# buses.net
KiCad netlist of a schematic drawn in EAGLE
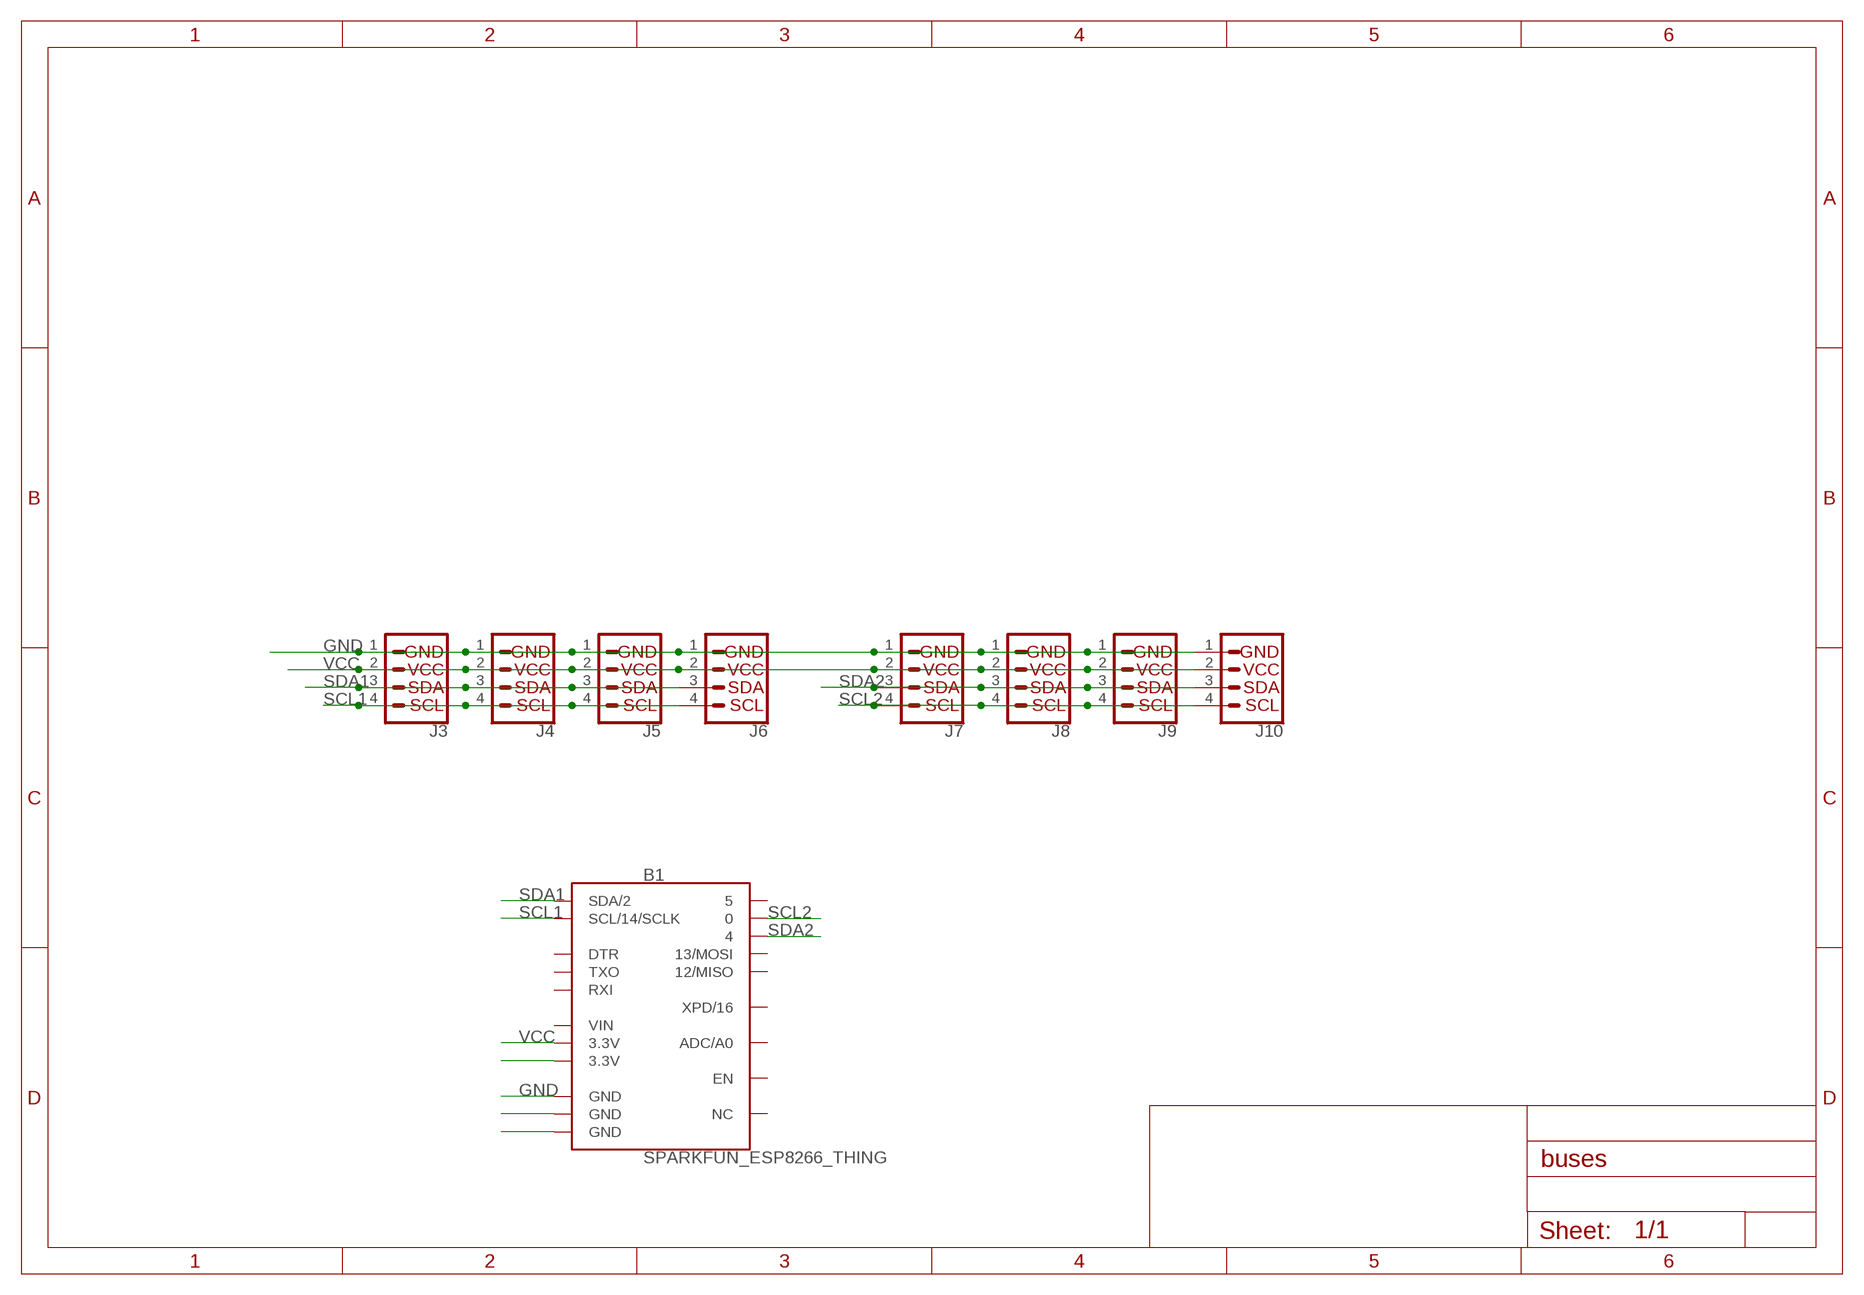
[diagram p0: schematic, sheet 1]

(export (version "E")
  (design (tool "Eeschema 10.0.6"))
  (components
    (comp (ref "B1")
      (value "SPARKFUN_ESP8266_THING")
      (footprint "eagle-import:SPARKFUN_ESP8266_THING")
      (libsource (lib "eagle-import") (part "SPARKFUN_ESP8266_THING"))
    )
    (comp (ref "J3")
      (value "I2C_STANDARD")
      (footprint "eagle-import:1X04")
      (libsource (lib "eagle-import") (part "I2C_STANDARD"))
    )
    (comp (ref "J4")
      (value "I2C_STANDARD")
      (footprint "eagle-import:1X04")
      (libsource (lib "eagle-import") (part "I2C_STANDARD"))
    )
    (comp (ref "J5")
      (value "I2C_STANDARD")
      (footprint "eagle-import:1X04")
      (libsource (lib "eagle-import") (part "I2C_STANDARD"))
    )
    (comp (ref "J6")
      (value "I2C_STANDARD")
      (footprint "eagle-import:1X04")
      (libsource (lib "eagle-import") (part "I2C_STANDARD"))
    )
    (comp (ref "J7")
      (value "I2C_STANDARD")
      (footprint "eagle-import:1X04")
      (libsource (lib "eagle-import") (part "I2C_STANDARD"))
    )
    (comp (ref "J8")
      (value "I2C_STANDARD")
      (footprint "eagle-import:1X04")
      (libsource (lib "eagle-import") (part "I2C_STANDARD"))
    )
    (comp (ref "J9")
      (value "I2C_STANDARD")
      (footprint "eagle-import:1X04")
      (libsource (lib "eagle-import") (part "I2C_STANDARD"))
    )
    (comp (ref "J10")
      (value "I2C_STANDARD")
      (footprint "eagle-import:1X04")
      (libsource (lib "eagle-import") (part "I2C_STANDARD"))
    )
  )
  (nets
    (net (code "1") (name "/GND") (class "Default")
      (node (ref "B1") (pin "GND@1") (pinfunction "GND_GND@1") (pintype "power_in"))
      (node (ref "B1") (pin "GND@2") (pinfunction "GND_GND@2") (pintype "power_in"))
      (node (ref "B1") (pin "GND@3") (pinfunction "GND_GND@3") (pintype "power_in"))
      (node (ref "J10") (pin "1") (pinfunction "1_1") (pintype "power_in"))
      (node (ref "J3") (pin "1") (pinfunction "1_1") (pintype "power_in"))
      (node (ref "J4") (pin "1") (pinfunction "1_1") (pintype "power_in"))
      (node (ref "J5") (pin "1") (pinfunction "1_1") (pintype "power_in"))
      (node (ref "J6") (pin "1") (pinfunction "1_1") (pintype "power_in"))
      (node (ref "J7") (pin "1") (pinfunction "1_1") (pintype "power_in"))
      (node (ref "J8") (pin "1") (pinfunction "1_1") (pintype "power_in"))
      (node (ref "J9") (pin "1") (pinfunction "1_1") (pintype "power_in"))
    )
    (net (code "2") (name "/SCL1") (class "Default")
      (node (ref "B1") (pin "SCL") (pinfunction "SCL/14/SCLK_SCL") (pintype "bidirectional"))
      (node (ref "J3") (pin "4") (pinfunction "4_4") (pintype "passive"))
      (node (ref "J4") (pin "4") (pinfunction "4_4") (pintype "passive"))
      (node (ref "J5") (pin "4") (pinfunction "4_4") (pintype "passive"))
      (node (ref "J6") (pin "4") (pinfunction "4_4") (pintype "passive"))
    )
    (net (code "3") (name "/SCL2") (class "Default")
      (node (ref "B1") (pin "0") (pinfunction "0_0") (pintype "bidirectional"))
      (node (ref "J10") (pin "4") (pinfunction "4_4") (pintype "passive"))
      (node (ref "J7") (pin "4") (pinfunction "4_4") (pintype "passive"))
      (node (ref "J8") (pin "4") (pinfunction "4_4") (pintype "passive"))
      (node (ref "J9") (pin "4") (pinfunction "4_4") (pintype "passive"))
    )
    (net (code "4") (name "/SDA1") (class "Default")
      (node (ref "B1") (pin "SDA") (pinfunction "SDA/2_SDA") (pintype "bidirectional"))
      (node (ref "J3") (pin "3") (pinfunction "3_3") (pintype "passive"))
      (node (ref "J4") (pin "3") (pinfunction "3_3") (pintype "passive"))
      (node (ref "J5") (pin "3") (pinfunction "3_3") (pintype "passive"))
      (node (ref "J6") (pin "3") (pinfunction "3_3") (pintype "passive"))
    )
    (net (code "5") (name "/SDA2") (class "Default")
      (node (ref "B1") (pin "4") (pinfunction "4_4") (pintype "bidirectional"))
      (node (ref "J10") (pin "3") (pinfunction "3_3") (pintype "passive"))
      (node (ref "J7") (pin "3") (pinfunction "3_3") (pintype "passive"))
      (node (ref "J8") (pin "3") (pinfunction "3_3") (pintype "passive"))
      (node (ref "J9") (pin "3") (pinfunction "3_3") (pintype "passive"))
    )
    (net (code "6") (name "/VCC") (class "Default")
      (node (ref "B1") (pin "3.3V@1") (pinfunction "3.3V_3.3V@1") (pintype "power_in"))
      (node (ref "B1") (pin "3.3V@2") (pinfunction "3.3V_3.3V@2") (pintype "power_in"))
      (node (ref "J10") (pin "2") (pinfunction "2_2") (pintype "power_in"))
      (node (ref "J3") (pin "2") (pinfunction "2_2") (pintype "power_in"))
      (node (ref "J4") (pin "2") (pinfunction "2_2") (pintype "power_in"))
      (node (ref "J5") (pin "2") (pinfunction "2_2") (pintype "power_in"))
      (node (ref "J6") (pin "2") (pinfunction "2_2") (pintype "power_in"))
      (node (ref "J7") (pin "2") (pinfunction "2_2") (pintype "power_in"))
      (node (ref "J8") (pin "2") (pinfunction "2_2") (pintype "power_in"))
      (node (ref "J9") (pin "2") (pinfunction "2_2") (pintype "power_in"))
    )
    (net (code "7") (name "/VIN") (class "Default")
      (node (ref "B1") (pin "VIN") (pinfunction "VIN_VIN") (pintype "power_in"))
    )
    (net (code "8") (name "unconnected-(B1-12{slash}MISO-Pad12)") (class "Default")
      (node (ref "B1") (pin "12") (pinfunction "12/MISO_12") (pintype "bidirectional"))
    )
    (net (code "9") (name "unconnected-(B1-13{slash}MOSI-Pad13)") (class "Default")
      (node (ref "B1") (pin "13") (pinfunction "13/MOSI_13") (pintype "bidirectional"))
    )
    (net (code "10") (name "unconnected-(B1-ADC{slash}A0-PadADC)") (class "Default")
      (node (ref "B1") (pin "ADC") (pinfunction "ADC/A0_ADC") (pintype "bidirectional"))
    )
    (net (code "11") (name "unconnected-(B1-Pad5)") (class "Default")
      (node (ref "B1") (pin "5") (pinfunction "5_5") (pintype "bidirectional"))
    )
    (net (code "12") (name "unconnected-(B1-PadDTR)") (class "Default")
      (node (ref "B1") (pin "DTR") (pinfunction "DTR_DTR") (pintype "bidirectional"))
    )
    (net (code "13") (name "unconnected-(B1-PadEN)") (class "Default")
      (node (ref "B1") (pin "EN") (pinfunction "EN_EN") (pintype "input"))
    )
    (net (code "14") (name "unconnected-(B1-PadNC)") (class "Default")
      (node (ref "B1") (pin "NC") (pinfunction "NC_NC") (pintype "no_connect"))
    )
    (net (code "15") (name "unconnected-(B1-PadRXI)") (class "Default")
      (node (ref "B1") (pin "RXI") (pinfunction "RXI_RXI") (pintype "input"))
    )
    (net (code "16") (name "unconnected-(B1-PadTXO)") (class "Default")
      (node (ref "B1") (pin "TXO") (pinfunction "TXO_TXO") (pintype "output"))
    )
    (net (code "17") (name "unconnected-(B1-XPD{slash}16-PadXPD)") (class "Default")
      (node (ref "B1") (pin "XPD") (pinfunction "XPD/16_XPD") (pintype "bidirectional"))
    )
  )
)
